# STM32.net
KiCad netlist of a schematic drawn in Altium Designer
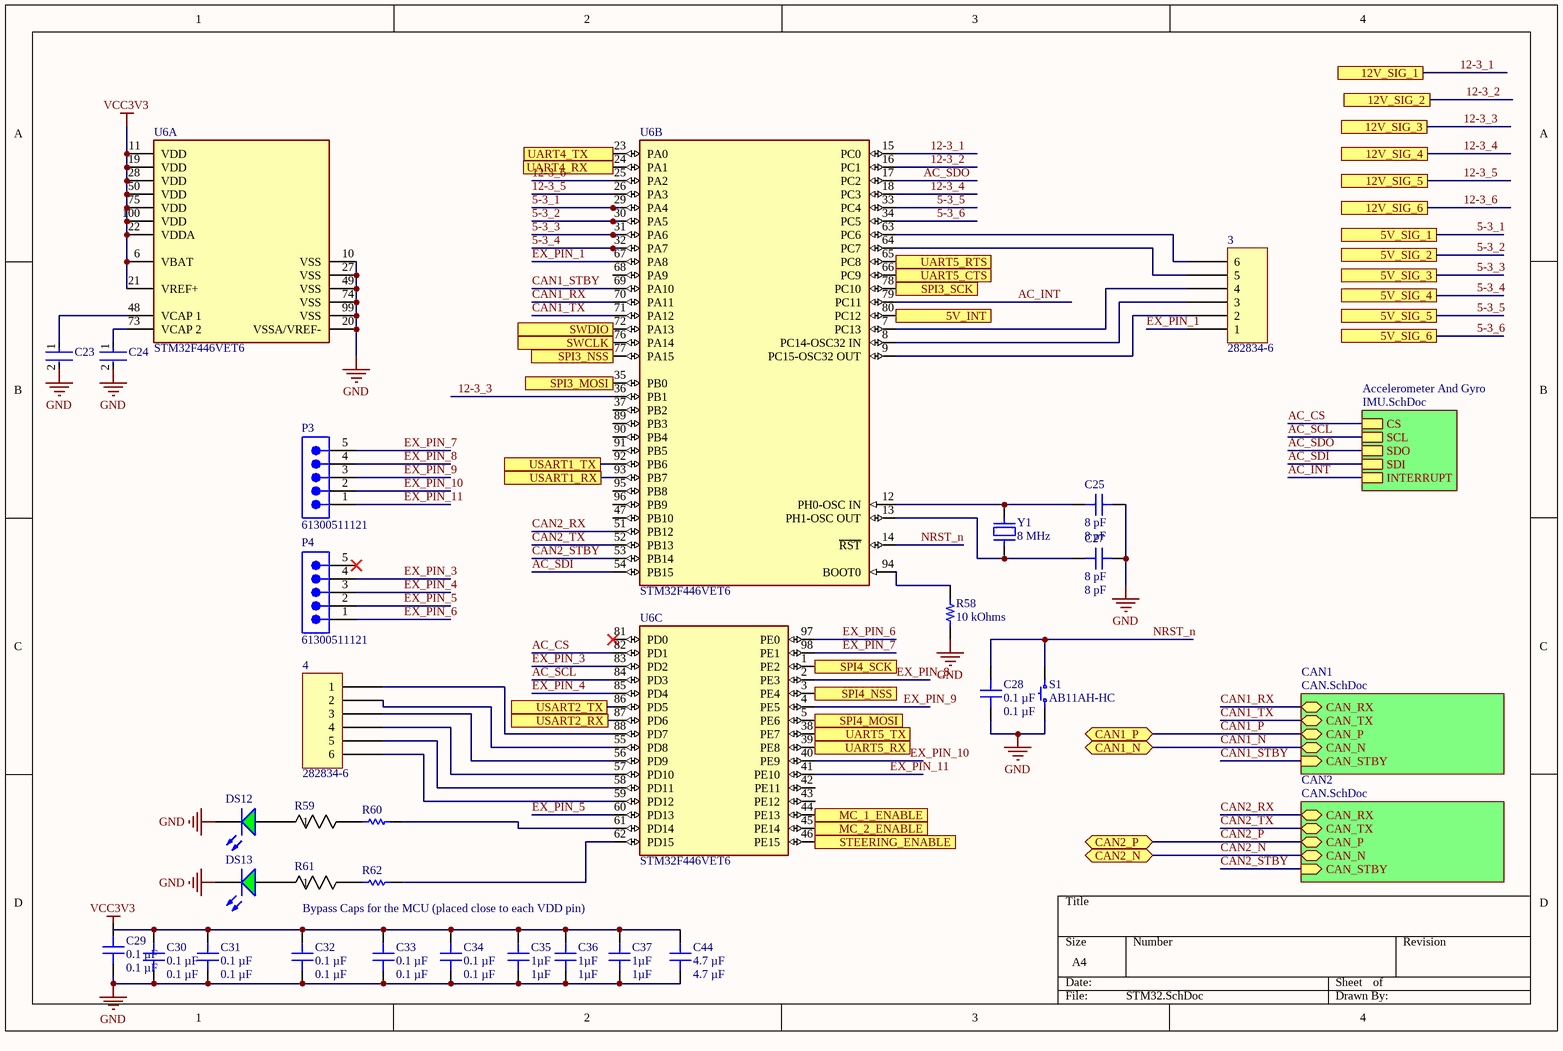
[diagram p0: STM32.SchDoc]

(export (version "E")
  (design (tool "Eeschema 10.0.6"))
  (components
    (comp (ref "3")
      (value "282834-6")
      (footprint "TE 282834-6")
      (description "TERM BLK 6P SIDE ENT 2.54MM PCB")
      (fields (field (name "MANUFACTURER") "TE Connectivity AMP Connectors") (field (name "VOLTAGE") "150V"))
      (libsource (lib "Celestial Altium Library - altium_library") (part "6 Pin"))
    )
    (comp (ref "4")
      (value "282834-6")
      (footprint "TE 282834-6")
      (description "TERM BLK 6P SIDE ENT 2.54MM PCB")
      (fields (field (name "MANUFACTURER") "TE Connectivity AMP Connectors") (field (name "VOLTAGE") "150V"))
      (libsource (lib "") (part "6 Pin_1"))
    )
    (comp (ref "C23")
      (value "GRM188R71A225KE15D")
      (footprint "FP-GRM188-0_1-e0_2_0_5-MFG")
      (description "Chip Multilayer Ceramic Capacitors for General Purpose, 0603, 2.2uF, X7R, 15%, 10%, 10V")
      (fields (field (name "VOLTAGE") "10V") (field (name "TOLERANCE") "10%"))
      (libsource (lib "Altium Content Vault") (part "11868f565c42a9108669ba33697ecf6"))
    )
    (comp (ref "C24")
      (value "GRM188R71A225KE15D")
      (footprint "FP-GRM188-0_1-e0_2_0_5-MFG")
      (description "Chip Multilayer Ceramic Capacitors for General Purpose, 0603, 2.2uF, X7R, 15%, 10%, 10V")
      (fields (field (name "VOLTAGE") "10V") (field (name "TOLERANCE") "10%"))
      (libsource (lib "Altium Content Vault") (part "11868f565c42a9108669ba33697ecf6"))
    )
    (comp (ref "C25")
      (value "8 pF")
      (footprint "CAP 0805_2012")
      (description "CAP CER 8PF 250V C0G/NP0 0805")
      (fields (field (name "PART NUMBER") "CBR08C809CAGAC") (field (name "ALTIUM_VALUE") "8 pF"))
      (libsource (lib "Celestial Altium Library - altium_library") (part "Capacitor"))
    )
    (comp (ref "C27")
      (value "8 pF")
      (footprint "CAP 0805_2012")
      (description "CAP CER 8PF 250V C0G/NP0 0805")
      (fields (field (name "PART NUMBER") "CBR08C809CAGAC") (field (name "ALTIUM_VALUE") "8 pF"))
      (libsource (lib "Celestial Altium Library - altium_library") (part "Capacitor"))
    )
    (comp (ref "C28")
      (value "0.1 µF")
      (footprint "CAP 0805_2012")
      (description "CAP CER 0.1UF 50V X7R 0805")
      (fields (field (name "PART NUMBER") "CC0805MRX7R9BB104") (field (name "ALTIUM_VALUE") "0.1 µF"))
      (libsource (lib "Celestial Altium Library - altium_library") (part "Capacitor"))
    )
    (comp (ref "C29")
      (value "0.1 µF")
      (footprint "CAP 0805_2012")
      (description "CAP CER 0.1UF 50V X7R 0805")
      (fields (field (name "PART NUMBER") "CC0805MRX7R9BB104") (field (name "ALTIUM_VALUE") "0.1 µF"))
      (libsource (lib "Celestial Altium Library - altium_library") (part "Capacitor"))
    )
    (comp (ref "C30")
      (value "0.1 µF")
      (footprint "CAP 0805_2012")
      (description "CAP CER 0.1UF 50V X7R 0805")
      (fields (field (name "PART NUMBER") "CC0805MRX7R9BB104") (field (name "ALTIUM_VALUE") "0.1 µF"))
      (libsource (lib "Celestial Altium Library - altium_library") (part "Capacitor"))
    )
    (comp (ref "C31")
      (value "0.1 µF")
      (footprint "CAP 0805_2012")
      (description "CAP CER 0.1UF 50V X7R 0805")
      (fields (field (name "PART NUMBER") "CC0805MRX7R9BB104") (field (name "ALTIUM_VALUE") "0.1 µF"))
      (libsource (lib "Celestial Altium Library - altium_library") (part "Capacitor"))
    )
    (comp (ref "C32")
      (value "0.1 µF")
      (footprint "CAP 0805_2012")
      (description "CAP CER 0.1UF 50V X7R 0805")
      (fields (field (name "PART NUMBER") "CC0805MRX7R9BB104") (field (name "ALTIUM_VALUE") "0.1 µF"))
      (libsource (lib "Celestial Altium Library - altium_library") (part "Capacitor"))
    )
    (comp (ref "C33")
      (value "0.1 µF")
      (footprint "CAP 0805_2012")
      (description "CAP CER 0.1UF 50V X7R 0805")
      (fields (field (name "PART NUMBER") "CC0805MRX7R9BB104") (field (name "ALTIUM_VALUE") "0.1 µF"))
      (libsource (lib "Celestial Altium Library - altium_library") (part "Capacitor"))
    )
    (comp (ref "C34")
      (value "0.1 µF")
      (footprint "CAP 0805_2012")
      (description "CAP CER 0.1UF 50V X7R 0805")
      (fields (field (name "PART NUMBER") "CC0805MRX7R9BB104") (field (name "ALTIUM_VALUE") "0.1 µF"))
      (libsource (lib "Celestial Altium Library - altium_library") (part "Capacitor"))
    )
    (comp (ref "C35")
      (value "1µF")
      (footprint "CAP 0805_2012")
      (description "CAP CER 1UF 10V X7R 0805")
      (fields (field (name "PART NUMBER") "MM05ZC105KCZ2A") (field (name "ALTIUM_VALUE") "1µF"))
      (libsource (lib "Celestial Altium Library - altium_library") (part "Capacitor"))
    )
    (comp (ref "C36")
      (value "1µF")
      (footprint "CAP 0805_2012")
      (description "CAP CER 1UF 10V X7R 0805")
      (fields (field (name "PART NUMBER") "MM05ZC105KCZ2A") (field (name "ALTIUM_VALUE") "1µF"))
      (libsource (lib "Celestial Altium Library - altium_library") (part "Capacitor"))
    )
    (comp (ref "C37")
      (value "1µF")
      (footprint "CAP 0805_2012")
      (description "CAP CER 1UF 10V X7R 0805")
      (fields (field (name "PART NUMBER") "MM05ZC105KCZ2A") (field (name "ALTIUM_VALUE") "1µF"))
      (libsource (lib "Celestial Altium Library - altium_library") (part "Capacitor"))
    )
    (comp (ref "C44")
      (value "4.7 µF")
      (footprint "CAP 0805_2012")
      (description "CAP CER 4.7UF 6.3V X7R 0805")
      (fields (field (name "PART NUMBER") "C0805X475J9RACAUTO") (field (name "ALTIUM_VALUE") "4.7 µF"))
      (libsource (lib "Celestial Altium Library - altium_library") (part "Capacitor"))
    )
    (comp (ref "DS12")
      (value "HLMP-4740")
      (footprint "AVAG-HLMP-4740")
      (description "T-1 3/4 (5 mm) Low Current LED Lamp, Green, 1.9 V, -20 to 100 degC, 2-Pin THD, RoHS, Bulk")
      (fields (field (name "MANUFACTURER") "AvagoTechnologies"))
      (libsource (lib "Altium Content Vault") (part "LED-GREEN-AK-2"))
    )
    (comp (ref "DS13")
      (value "HLMP-4740")
      (footprint "AVAG-HLMP-4740")
      (description "T-1 3/4 (5 mm) Low Current LED Lamp, Green, 1.9 V, -20 to 100 degC, 2-Pin THD, RoHS, Bulk")
      (fields (field (name "MANUFACTURER") "AvagoTechnologies"))
      (libsource (lib "Altium Content Vault") (part "LED-GREEN-AK-2"))
    )
    (comp (ref "P3")
      (value "61300511121")
      (footprint "61300511121")
      (libsource (lib "Altium Content Vault") (part "Header_Male_1R_05P"))
    )
    (comp (ref "P4")
      (value "61300511121")
      (footprint "61300511121")
      (libsource (lib "Altium Content Vault") (part "Header_Male_1R_05P"))
    )
    (comp (ref "R58")
      (value "10 kOhms")
      (footprint "RES 0805_2012")
      (description "RES 10K OHM 0.1% 1/10W 0805")
      (fields
        (field (name "PART NUMBER") "RNCS0805BKE10K0")
        (field (name "MANUFACTURER") "Stackpole Electronics Inc")
      )
      (libsource (lib "Celestial Altium Library - altium_library") (part "Resistor"))
    )
    (comp (ref "R59")
      (value "AC01000005000JA100")
      (footprint "RES_AC01_VIS")
      (fields (field (name "TOLERANCE") "5%"))
      (libsource (lib "Altium Content Vault") (part "AC01000005000JA100"))
    )
    (comp (ref "R60")
      (value "RC0805FR-071KL")
      (footprint "RESC2013X60X35ML10T20")
      (description "Chip Resistor, 1 KOhm, +/- 1%, 125 mW, -55 to 155 degC, 0805 (2012 Metric), RoHS, Tape and Reel")
      (fields (field (name "TOLERANCE") "1%") (field (name "MANUFACTURER") "Yageo"))
      (libsource (lib "Altium Content Vault") (part "RES-2"))
    )
    (comp (ref "R61")
      (value "AC01000005000JA100")
      (footprint "RES_AC01_VIS")
      (fields (field (name "TOLERANCE") "5%"))
      (libsource (lib "Altium Content Vault") (part "AC01000005000JA100"))
    )
    (comp (ref "R62")
      (value "RC0805FR-071KL")
      (footprint "RESC2013X60X35ML10T20")
      (description "Chip Resistor, 1 KOhm, +/- 1%, 125 mW, -55 to 155 degC, 0805 (2012 Metric), RoHS, Tape and Reel")
      (fields (field (name "TOLERANCE") "1%") (field (name "MANUFACTURER") "Yageo"))
      (libsource (lib "Altium Content Vault") (part "RES-2"))
    )
    (comp (ref "S1")
      (value "AB11AH-HC")
      (footprint "NKK AB11AH-HC")
      (description "SWITCH PUSH SPST-NO 0.4VA 28V")
      (fields (field (name "MANUFACTURER") "NKK Switches"))
      (libsource (lib "Celestial Altium Library - altium_library") (part "SPST-NO 2 PIN"))
    )
    (comp (ref "U6")
      (value "STM32F446VET6")
      (footprint "FP-LQFP100-1L-MFG")
      (description "IC MCU 32BIT 512KB FLASH 100LQFP")
      (fields
        (field (name "OCTOPART") "https://octopart.com/stm32f446vet6-stmicroelectronics-52642922")
        (field (name "MANUFACTURER") "STMicroelectronics")
      )
      (libsource (lib "Altium Content Vault") (part "8e3e88e6cb74ec1f9e49940598abbc7"))
    )
    (comp (ref "Y1")
      (value "8 MHz")
      (footprint "ABRACON ABLS")
      (description "CRYSTAL 8.0000MHZ 18PF SMD")
      (fields (field (name "PART NUMBER") "ABLS-8.000MHZ-SD7Y-T") (field (name "MANUFACTURER") "Abracon LLC"))
      (libsource (lib "Celestial Altium Library - altium_library") (part "Abracon Crystal ABLS"))
    )
  )
  (nets
    (net (code "1") (name "/5-3_1") (class "Default")
      (node (ref "U6") (pin "29") (pinfunction "PA4_29") (pintype "bidirectional"))
    )
    (net (code "2") (name "/5-3_2") (class "Default")
      (node (ref "U6") (pin "30") (pinfunction "PA5_30") (pintype "bidirectional"))
    )
    (net (code "3") (name "/5-3_3") (class "Default")
      (node (ref "U6") (pin "31") (pinfunction "PA6_31") (pintype "bidirectional"))
    )
    (net (code "4") (name "/5-3_4") (class "Default")
      (node (ref "U6") (pin "32") (pinfunction "PA7_32") (pintype "bidirectional"))
    )
    (net (code "5") (name "/5-3_5") (class "Default")
      (node (ref "U6") (pin "33") (pinfunction "PC4_33") (pintype "bidirectional"))
    )
    (net (code "6") (name "/5-3_6") (class "Default")
      (node (ref "U6") (pin "34") (pinfunction "PC5_34") (pintype "bidirectional"))
    )
    (net (code "7") (name "/5V_INT") (class "Default")
      (node (ref "U6") (pin "80") (pinfunction "PC12_80") (pintype "bidirectional"))
    )
    (net (code "8") (name "/12-3_1") (class "Default")
      (node (ref "U6") (pin "15") (pinfunction "PC0_15") (pintype "bidirectional"))
    )
    (net (code "9") (name "/12-3_2") (class "Default")
      (node (ref "U6") (pin "16") (pinfunction "PC1_16") (pintype "bidirectional"))
    )
    (net (code "10") (name "/12-3_3") (class "Default")
      (node (ref "U6") (pin "36") (pinfunction "PB1_36") (pintype "bidirectional"))
    )
    (net (code "11") (name "/12-3_4") (class "Default")
      (node (ref "U6") (pin "18") (pinfunction "PC3_18") (pintype "bidirectional"))
    )
    (net (code "12") (name "/12-3_5") (class "Default")
      (node (ref "U6") (pin "26") (pinfunction "PA3_26") (pintype "bidirectional"))
    )
    (net (code "13") (name "/12-3_6") (class "Default")
      (node (ref "U6") (pin "25") (pinfunction "PA2_25") (pintype "bidirectional"))
    )
    (net (code "14") (name "/AC_CS") (class "Default")
      (node (ref "U6") (pin "82") (pinfunction "PD1_82") (pintype "bidirectional"))
    )
    (net (code "15") (name "/AC_INT") (class "Default")
      (node (ref "U6") (pin "79") (pinfunction "PC11_79") (pintype "bidirectional"))
    )
    (net (code "16") (name "/AC_SCL") (class "Default")
      (node (ref "U6") (pin "84") (pinfunction "PD3_84") (pintype "bidirectional"))
    )
    (net (code "17") (name "/AC_SDI") (class "Default")
      (node (ref "U6") (pin "54") (pinfunction "PB15_54") (pintype "bidirectional"))
    )
    (net (code "18") (name "/AC_SDO") (class "Default")
      (node (ref "U6") (pin "17") (pinfunction "PC2_17") (pintype "bidirectional"))
    )
    (net (code "21") (name "/CAN1_RX") (class "Default")
      (node (ref "U6") (pin "70") (pinfunction "PA11_70") (pintype "bidirectional"))
    )
    (net (code "22") (name "/CAN1_STBY") (class "Default")
      (node (ref "U6") (pin "69") (pinfunction "PA10_69") (pintype "bidirectional"))
    )
    (net (code "23") (name "/CAN1_TX") (class "Default")
      (node (ref "U6") (pin "71") (pinfunction "PA12_71") (pintype "bidirectional"))
    )
    (net (code "26") (name "/CAN2_RX") (class "Default")
      (node (ref "U6") (pin "51") (pinfunction "PB12_51") (pintype "bidirectional"))
    )
    (net (code "27") (name "/CAN2_STBY") (class "Default")
      (node (ref "U6") (pin "53") (pinfunction "PB14_53") (pintype "bidirectional"))
    )
    (net (code "28") (name "/CAN2_TX") (class "Default")
      (node (ref "U6") (pin "52") (pinfunction "PB13_52") (pintype "bidirectional"))
    )
    (net (code "29") (name "/EX_PIN_1") (class "Default")
      (node (ref "3") (pin "1") (pinfunction "1_1") (pintype "passive"))
      (node (ref "U6") (pin "67") (pinfunction "PA8_67") (pintype "bidirectional"))
    )
    (net (code "30") (name "/EX_PIN_3") (class "Default")
      (node (ref "P4") (pin "4") (pinfunction "4_4") (pintype "passive"))
      (node (ref "U6") (pin "83") (pinfunction "PD2_83") (pintype "bidirectional"))
    )
    (net (code "31") (name "/EX_PIN_4") (class "Default")
      (node (ref "P4") (pin "3") (pinfunction "3_3") (pintype "passive"))
      (node (ref "U6") (pin "85") (pinfunction "PD4_85") (pintype "bidirectional"))
    )
    (net (code "32") (name "/EX_PIN_5") (class "Default")
      (node (ref "P4") (pin "2") (pinfunction "2_2") (pintype "passive"))
      (node (ref "U6") (pin "60") (pinfunction "PD13_60") (pintype "bidirectional"))
    )
    (net (code "33") (name "/EX_PIN_6") (class "Default")
      (node (ref "P4") (pin "1") (pinfunction "1_1") (pintype "passive"))
      (node (ref "U6") (pin "97") (pinfunction "PE0_97") (pintype "bidirectional"))
    )
    (net (code "34") (name "/EX_PIN_7") (class "Default")
      (node (ref "P3") (pin "5") (pinfunction "5_5") (pintype "passive"))
      (node (ref "U6") (pin "98") (pinfunction "PE1_98") (pintype "bidirectional"))
    )
    (net (code "35") (name "/EX_PIN_8") (class "Default")
      (node (ref "P3") (pin "4") (pinfunction "4_4") (pintype "passive"))
      (node (ref "U6") (pin "2") (pinfunction "PE3_2") (pintype "bidirectional"))
    )
    (net (code "36") (name "/EX_PIN_9") (class "Default")
      (node (ref "P3") (pin "3") (pinfunction "3_3") (pintype "passive"))
      (node (ref "U6") (pin "4") (pinfunction "PE5_4") (pintype "bidirectional"))
    )
    (net (code "37") (name "/EX_PIN_10") (class "Default")
      (node (ref "P3") (pin "2") (pinfunction "2_2") (pintype "passive"))
      (node (ref "U6") (pin "40") (pinfunction "PE9_40") (pintype "bidirectional"))
    )
    (net (code "38") (name "/EX_PIN_11") (class "Default")
      (node (ref "P3") (pin "1") (pinfunction "1_1") (pintype "passive"))
      (node (ref "U6") (pin "41") (pinfunction "PE10_41") (pintype "bidirectional"))
    )
    (net (code "39") (name "/MC_1_ENABLE") (class "Default")
      (node (ref "U6") (pin "44") (pinfunction "PE13_44") (pintype "bidirectional"))
    )
    (net (code "40") (name "/MC_2_ENABLE") (class "Default")
      (node (ref "U6") (pin "45") (pinfunction "PE14_45") (pintype "bidirectional"))
    )
    (net (code "41") (name "/NRST_n") (class "Default")
      (node (ref "C28") (pin "2") (pinfunction "2_2") (pintype "passive"))
      (node (ref "S1") (pin "2") (pinfunction "2_2") (pintype "passive"))
      (node (ref "U6") (pin "14") (pinfunction "~{RST}_14") (pintype "bidirectional"))
    )
    (net (code "42") (name "/SPI3_MOSI") (class "Default")
      (node (ref "U6") (pin "35") (pinfunction "PB0_35") (pintype "bidirectional"))
    )
    (net (code "43") (name "/SPI3_NSS") (class "Default")
      (node (ref "U6") (pin "77") (pinfunction "PA15_77") (pintype "bidirectional"))
    )
    (net (code "44") (name "/SPI3_SCK") (class "Default")
      (node (ref "U6") (pin "78") (pinfunction "PC10_78") (pintype "bidirectional"))
    )
    (net (code "45") (name "/SPI4_MOSI") (class "Default")
      (node (ref "U6") (pin "5") (pinfunction "PE6_5") (pintype "bidirectional"))
    )
    (net (code "46") (name "/SPI4_NSS") (class "Default")
      (node (ref "U6") (pin "3") (pinfunction "PE4_3") (pintype "bidirectional"))
    )
    (net (code "47") (name "/SPI4_SCK") (class "Default")
      (node (ref "U6") (pin "1") (pinfunction "PE2_1") (pintype "bidirectional"))
    )
    (net (code "48") (name "/STEERING_ENABLE") (class "Default")
      (node (ref "U6") (pin "46") (pinfunction "PE15_46") (pintype "bidirectional"))
    )
    (net (code "49") (name "/SWCLK") (class "Default")
      (node (ref "U6") (pin "76") (pinfunction "PA14_76") (pintype "bidirectional"))
    )
    (net (code "50") (name "/SWDIO") (class "Default")
      (node (ref "U6") (pin "72") (pinfunction "PA13_72") (pintype "bidirectional"))
    )
    (net (code "51") (name "/UART4_RX") (class "Default")
      (node (ref "U6") (pin "24") (pinfunction "PA1_24") (pintype "bidirectional"))
    )
    (net (code "52") (name "/UART4_TX") (class "Default")
      (node (ref "U6") (pin "23") (pinfunction "PA0_23") (pintype "bidirectional"))
    )
    (net (code "53") (name "/UART5_CTS") (class "Default")
      (node (ref "U6") (pin "66") (pinfunction "PC9_66") (pintype "bidirectional"))
    )
    (net (code "54") (name "/UART5_RTS") (class "Default")
      (node (ref "U6") (pin "65") (pinfunction "PC8_65") (pintype "bidirectional"))
    )
    (net (code "55") (name "/UART5_RX") (class "Default")
      (node (ref "U6") (pin "39") (pinfunction "PE8_39") (pintype "bidirectional"))
    )
    (net (code "56") (name "/UART5_TX") (class "Default")
      (node (ref "U6") (pin "38") (pinfunction "PE7_38") (pintype "bidirectional"))
    )
    (net (code "57") (name "/USART1_RX") (class "Default")
      (node (ref "U6") (pin "93") (pinfunction "PB7_93") (pintype "bidirectional"))
    )
    (net (code "58") (name "/USART1_TX") (class "Default")
      (node (ref "U6") (pin "92") (pinfunction "PB6_92") (pintype "bidirectional"))
    )
    (net (code "59") (name "/USART2_RX") (class "Default")
      (node (ref "U6") (pin "87") (pinfunction "PD6_87") (pintype "bidirectional"))
    )
    (net (code "60") (name "/USART2_TX") (class "Default")
      (node (ref "U6") (pin "86") (pinfunction "PD5_86") (pintype "bidirectional"))
    )
    (net (code "61") (name "GND") (class "Default")
      (node (ref "C23") (pin "2") (pinfunction "2_2") (pintype "passive"))
      (node (ref "C24") (pin "2") (pinfunction "2_2") (pintype "passive"))
      (node (ref "C25") (pin "2") (pinfunction "2_2") (pintype "passive"))
      (node (ref "C27") (pin "2") (pinfunction "2_2") (pintype "passive"))
      (node (ref "C28") (pin "1") (pinfunction "1_1") (pintype "passive"))
      (node (ref "C29") (pin "1") (pinfunction "1_1") (pintype "passive"))
      (node (ref "C30") (pin "1") (pinfunction "1_1") (pintype "passive"))
      (node (ref "C31") (pin "1") (pinfunction "1_1") (pintype "passive"))
      (node (ref "C32") (pin "1") (pinfunction "1_1") (pintype "passive"))
      (node (ref "C33") (pin "1") (pinfunction "1_1") (pintype "passive"))
      (node (ref "C34") (pin "1") (pinfunction "1_1") (pintype "passive"))
      (node (ref "C35") (pin "1") (pinfunction "1_1") (pintype "passive"))
      (node (ref "C36") (pin "1") (pinfunction "1_1") (pintype "passive"))
      (node (ref "C37") (pin "1") (pinfunction "1_1") (pintype "passive"))
      (node (ref "C44") (pin "1") (pinfunction "1_1") (pintype "passive"))
      (node (ref "DS12") (pin "2") (pinfunction "K_2") (pintype "passive"))
      (node (ref "DS13") (pin "2") (pinfunction "K_2") (pintype "passive"))
      (node (ref "R58") (pin "1") (pinfunction "1_1") (pintype "passive"))
      (node (ref "S1") (pin "1") (pinfunction "1_1") (pintype "passive"))
      (node (ref "U6") (pin "10") (pinfunction "VSS_10") (pintype "power_in"))
      (node (ref "U6") (pin "20") (pinfunction "VSSA/VREF-_20") (pintype "power_in"))
      (node (ref "U6") (pin "27") (pinfunction "VSS_27") (pintype "power_in"))
      (node (ref "U6") (pin "49") (pinfunction "VSS_49") (pintype "power_in"))
      (node (ref "U6") (pin "74") (pinfunction "VSS_74") (pintype "power_in"))
      (node (ref "U6") (pin "99") (pinfunction "VSS_99") (pintype "power_in"))
    )
    (net (code "62") (name "Net-(DS12-A)") (class "Default")
      (node (ref "DS12") (pin "1") (pinfunction "A_1") (pintype "passive"))
      (node (ref "R59") (pin "1") (pinfunction "1_1") (pintype "passive"))
    )
    (net (code "63") (name "Net-(DS13-A)") (class "Default")
      (node (ref "DS13") (pin "1") (pinfunction "A_1") (pintype "passive"))
      (node (ref "R61") (pin "1") (pinfunction "1_1") (pintype "passive"))
    )
    (net (code "64") (name "Net-(R59-Pad2)") (class "Default")
      (node (ref "R59") (pin "2") (pinfunction "2_2") (pintype "passive"))
      (node (ref "R60") (pin "1") (pinfunction "1_1") (pintype "passive"))
    )
    (net (code "65") (name "Net-(R61-Pad2)") (class "Default")
      (node (ref "R61") (pin "2") (pinfunction "2_2") (pintype "passive"))
      (node (ref "R62") (pin "1") (pinfunction "1_1") (pintype "passive"))
    )
    (net (code "66") (name "Net-(U6A-VCAP_1)") (class "Default")
      (node (ref "C23") (pin "1") (pinfunction "1_1") (pintype "passive"))
      (node (ref "U6") (pin "48") (pinfunction "VCAP_1_48") (pintype "power_in"))
    )
    (net (code "67") (name "Net-(U6A-VCAP_2)") (class "Default")
      (node (ref "C24") (pin "1") (pinfunction "1_1") (pintype "passive"))
      (node (ref "U6") (pin "73") (pinfunction "VCAP_2_73") (pintype "power_in"))
    )
    (net (code "68") (name "Net-(U6B-BOOT0)") (class "Default")
      (node (ref "R58") (pin "2") (pinfunction "2_2") (pintype "passive"))
      (node (ref "U6") (pin "94") (pinfunction "BOOT0_94") (pintype "input"))
    )
    (net (code "69") (name "Net-(U6B-PC6)") (class "Default")
      (node (ref "3") (pin "6") (pinfunction "6_6") (pintype "passive"))
      (node (ref "U6") (pin "63") (pinfunction "PC6_63") (pintype "bidirectional"))
    )
    (net (code "70") (name "Net-(U6B-PC7)") (class "Default")
      (node (ref "3") (pin "5") (pinfunction "5_5") (pintype "passive"))
      (node (ref "U6") (pin "64") (pinfunction "PC7_64") (pintype "bidirectional"))
    )
    (net (code "71") (name "Net-(U6B-PC13)") (class "Default")
      (node (ref "3") (pin "4") (pinfunction "4_4") (pintype "passive"))
      (node (ref "U6") (pin "7") (pinfunction "PC13_7") (pintype "bidirectional"))
    )
    (net (code "72") (name "Net-(U6B-PC14-OSC32_IN)") (class "Default")
      (node (ref "3") (pin "3") (pinfunction "3_3") (pintype "passive"))
      (node (ref "U6") (pin "8") (pinfunction "PC14-OSC32_IN_8") (pintype "bidirectional"))
    )
    (net (code "73") (name "Net-(U6B-PC15-OSC32_OUT)") (class "Default")
      (node (ref "3") (pin "2") (pinfunction "2_2") (pintype "passive"))
      (node (ref "U6") (pin "9") (pinfunction "PC15-OSC32_OUT_9") (pintype "bidirectional"))
    )
    (net (code "74") (name "Net-(U6B-PH0-OSC_IN)") (class "Default")
      (node (ref "C25") (pin "1") (pinfunction "1_1") (pintype "passive"))
      (node (ref "U6") (pin "12") (pinfunction "PH0-OSC_IN_12") (pintype "input"))
      (node (ref "Y1") (pin "2") (pinfunction "2_2") (pintype "passive"))
    )
    (net (code "75") (name "Net-(U6B-PH1-OSC_OUT)") (class "Default")
      (node (ref "C27") (pin "1") (pinfunction "1_1") (pintype "passive"))
      (node (ref "U6") (pin "13") (pinfunction "PH1-OSC_OUT_13") (pintype "bidirectional"))
      (node (ref "Y1") (pin "1") (pinfunction "1_1") (pintype "passive"))
    )
    (net (code "76") (name "Net-(U6C-PD7)") (class "Default")
      (node (ref "4") (pin "1") (pinfunction "1_1") (pintype "passive"))
      (node (ref "U6") (pin "88") (pinfunction "PD7_88") (pintype "bidirectional"))
    )
    (net (code "77") (name "Net-(U6C-PD8)") (class "Default")
      (node (ref "4") (pin "2") (pinfunction "2_2") (pintype "passive"))
      (node (ref "U6") (pin "55") (pinfunction "PD8_55") (pintype "bidirectional"))
    )
    (net (code "78") (name "Net-(U6C-PD9)") (class "Default")
      (node (ref "4") (pin "3") (pinfunction "3_3") (pintype "passive"))
      (node (ref "U6") (pin "56") (pinfunction "PD9_56") (pintype "bidirectional"))
    )
    (net (code "79") (name "Net-(U6C-PD10)") (class "Default")
      (node (ref "4") (pin "4") (pinfunction "4_4") (pintype "passive"))
      (node (ref "U6") (pin "57") (pinfunction "PD10_57") (pintype "bidirectional"))
    )
    (net (code "80") (name "Net-(U6C-PD11)") (class "Default")
      (node (ref "4") (pin "5") (pinfunction "5_5") (pintype "passive"))
      (node (ref "U6") (pin "58") (pinfunction "PD11_58") (pintype "bidirectional"))
    )
    (net (code "81") (name "Net-(U6C-PD12)") (class "Default")
      (node (ref "4") (pin "6") (pinfunction "6_6") (pintype "passive"))
      (node (ref "U6") (pin "59") (pinfunction "PD12_59") (pintype "bidirectional"))
    )
    (net (code "82") (name "Net-(U6C-PD14)") (class "Default")
      (node (ref "R60") (pin "2") (pinfunction "2_2") (pintype "passive"))
      (node (ref "U6") (pin "61") (pinfunction "PD14_61") (pintype "bidirectional"))
    )
    (net (code "83") (name "Net-(U6C-PD15)") (class "Default")
      (node (ref "R62") (pin "2") (pinfunction "2_2") (pintype "passive"))
      (node (ref "U6") (pin "62") (pinfunction "PD15_62") (pintype "bidirectional"))
    )
    (net (code "84") (name "VCC3V3") (class "Default")
      (node (ref "C30") (pin "2") (pinfunction "2_2") (pintype "passive"))
      (node (ref "C31") (pin "2") (pinfunction "2_2") (pintype "passive"))
      (node (ref "C32") (pin "2") (pinfunction "2_2") (pintype "passive"))
      (node (ref "C33") (pin "2") (pinfunction "2_2") (pintype "passive"))
      (node (ref "C34") (pin "2") (pinfunction "2_2") (pintype "passive"))
      (node (ref "C35") (pin "2") (pinfunction "2_2") (pintype "passive"))
      (node (ref "C36") (pin "2") (pinfunction "2_2") (pintype "passive"))
      (node (ref "C37") (pin "2") (pinfunction "2_2") (pintype "passive"))
      (node (ref "C44") (pin "2") (pinfunction "2_2") (pintype "passive"))
      (node (ref "U6") (pin "100") (pinfunction "VDD_100") (pintype "power_in"))
      (node (ref "U6") (pin "11") (pinfunction "VDD_11") (pintype "power_in"))
      (node (ref "U6") (pin "19") (pinfunction "VDD_19") (pintype "power_in"))
      (node (ref "U6") (pin "21") (pinfunction "VREF+_21") (pintype "power_in"))
      (node (ref "U6") (pin "22") (pinfunction "VDDA_22") (pintype "power_in"))
      (node (ref "U6") (pin "28") (pinfunction "VDD_28") (pintype "power_in"))
      (node (ref "U6") (pin "50") (pinfunction "VDD_50") (pintype "power_in"))
      (node (ref "U6") (pin "6") (pinfunction "VBAT_6") (pintype "power_in"))
      (node (ref "U6") (pin "75") (pinfunction "VDD_75") (pintype "power_in"))
    )
    (net (code "85") (name "unconnected-(C29-Pad2)") (class "Default")
      (node (ref "C29") (pin "2") (pinfunction "2_2") (pintype "passive"))
    )
    (net (code "86") (name "unconnected-(P4-Pad5)") (class "Default")
      (node (ref "P4") (pin "5") (pinfunction "5_5") (pintype "passive+no_connect"))
    )
    (net (code "87") (name "unconnected-(U6B-PA9-Pad68)") (class "Default")
      (node (ref "U6") (pin "68") (pinfunction "PA9_68") (pintype "bidirectional"))
    )
    (net (code "88") (name "unconnected-(U6B-PB2-Pad37)") (class "Default")
      (node (ref "U6") (pin "37") (pinfunction "PB2_37") (pintype "bidirectional"))
    )
    (net (code "89") (name "unconnected-(U6B-PB3-Pad89)") (class "Default")
      (node (ref "U6") (pin "89") (pinfunction "PB3_89") (pintype "bidirectional"))
    )
    (net (code "90") (name "unconnected-(U6B-PB4-Pad90)") (class "Default")
      (node (ref "U6") (pin "90") (pinfunction "PB4_90") (pintype "bidirectional"))
    )
    (net (code "91") (name "unconnected-(U6B-PB5-Pad91)") (class "Default")
      (node (ref "U6") (pin "91") (pinfunction "PB5_91") (pintype "bidirectional"))
    )
    (net (code "92") (name "unconnected-(U6B-PB8-Pad95)") (class "Default")
      (node (ref "U6") (pin "95") (pinfunction "PB8_95") (pintype "bidirectional"))
    )
    (net (code "93") (name "unconnected-(U6B-PB9-Pad96)") (class "Default")
      (node (ref "U6") (pin "96") (pinfunction "PB9_96") (pintype "bidirectional"))
    )
    (net (code "94") (name "unconnected-(U6B-PB10-Pad47)") (class "Default")
      (node (ref "U6") (pin "47") (pinfunction "PB10_47") (pintype "bidirectional"))
    )
    (net (code "95") (name "unconnected-(U6C-PD0-Pad81)") (class "Default")
      (node (ref "U6") (pin "81") (pinfunction "PD0_81") (pintype "bidirectional+no_connect"))
    )
    (net (code "96") (name "unconnected-(U6C-PE11-Pad42)") (class "Default")
      (node (ref "U6") (pin "42") (pinfunction "PE11_42") (pintype "bidirectional"))
    )
    (net (code "97") (name "unconnected-(U6C-PE12-Pad43)") (class "Default")
      (node (ref "U6") (pin "43") (pinfunction "PE12_43") (pintype "bidirectional"))
    )
  )
)
